# SCH_Line-Follower-proof-of-concepts_2025.net
KiCad netlist of a schematic drawn in EasyEDA
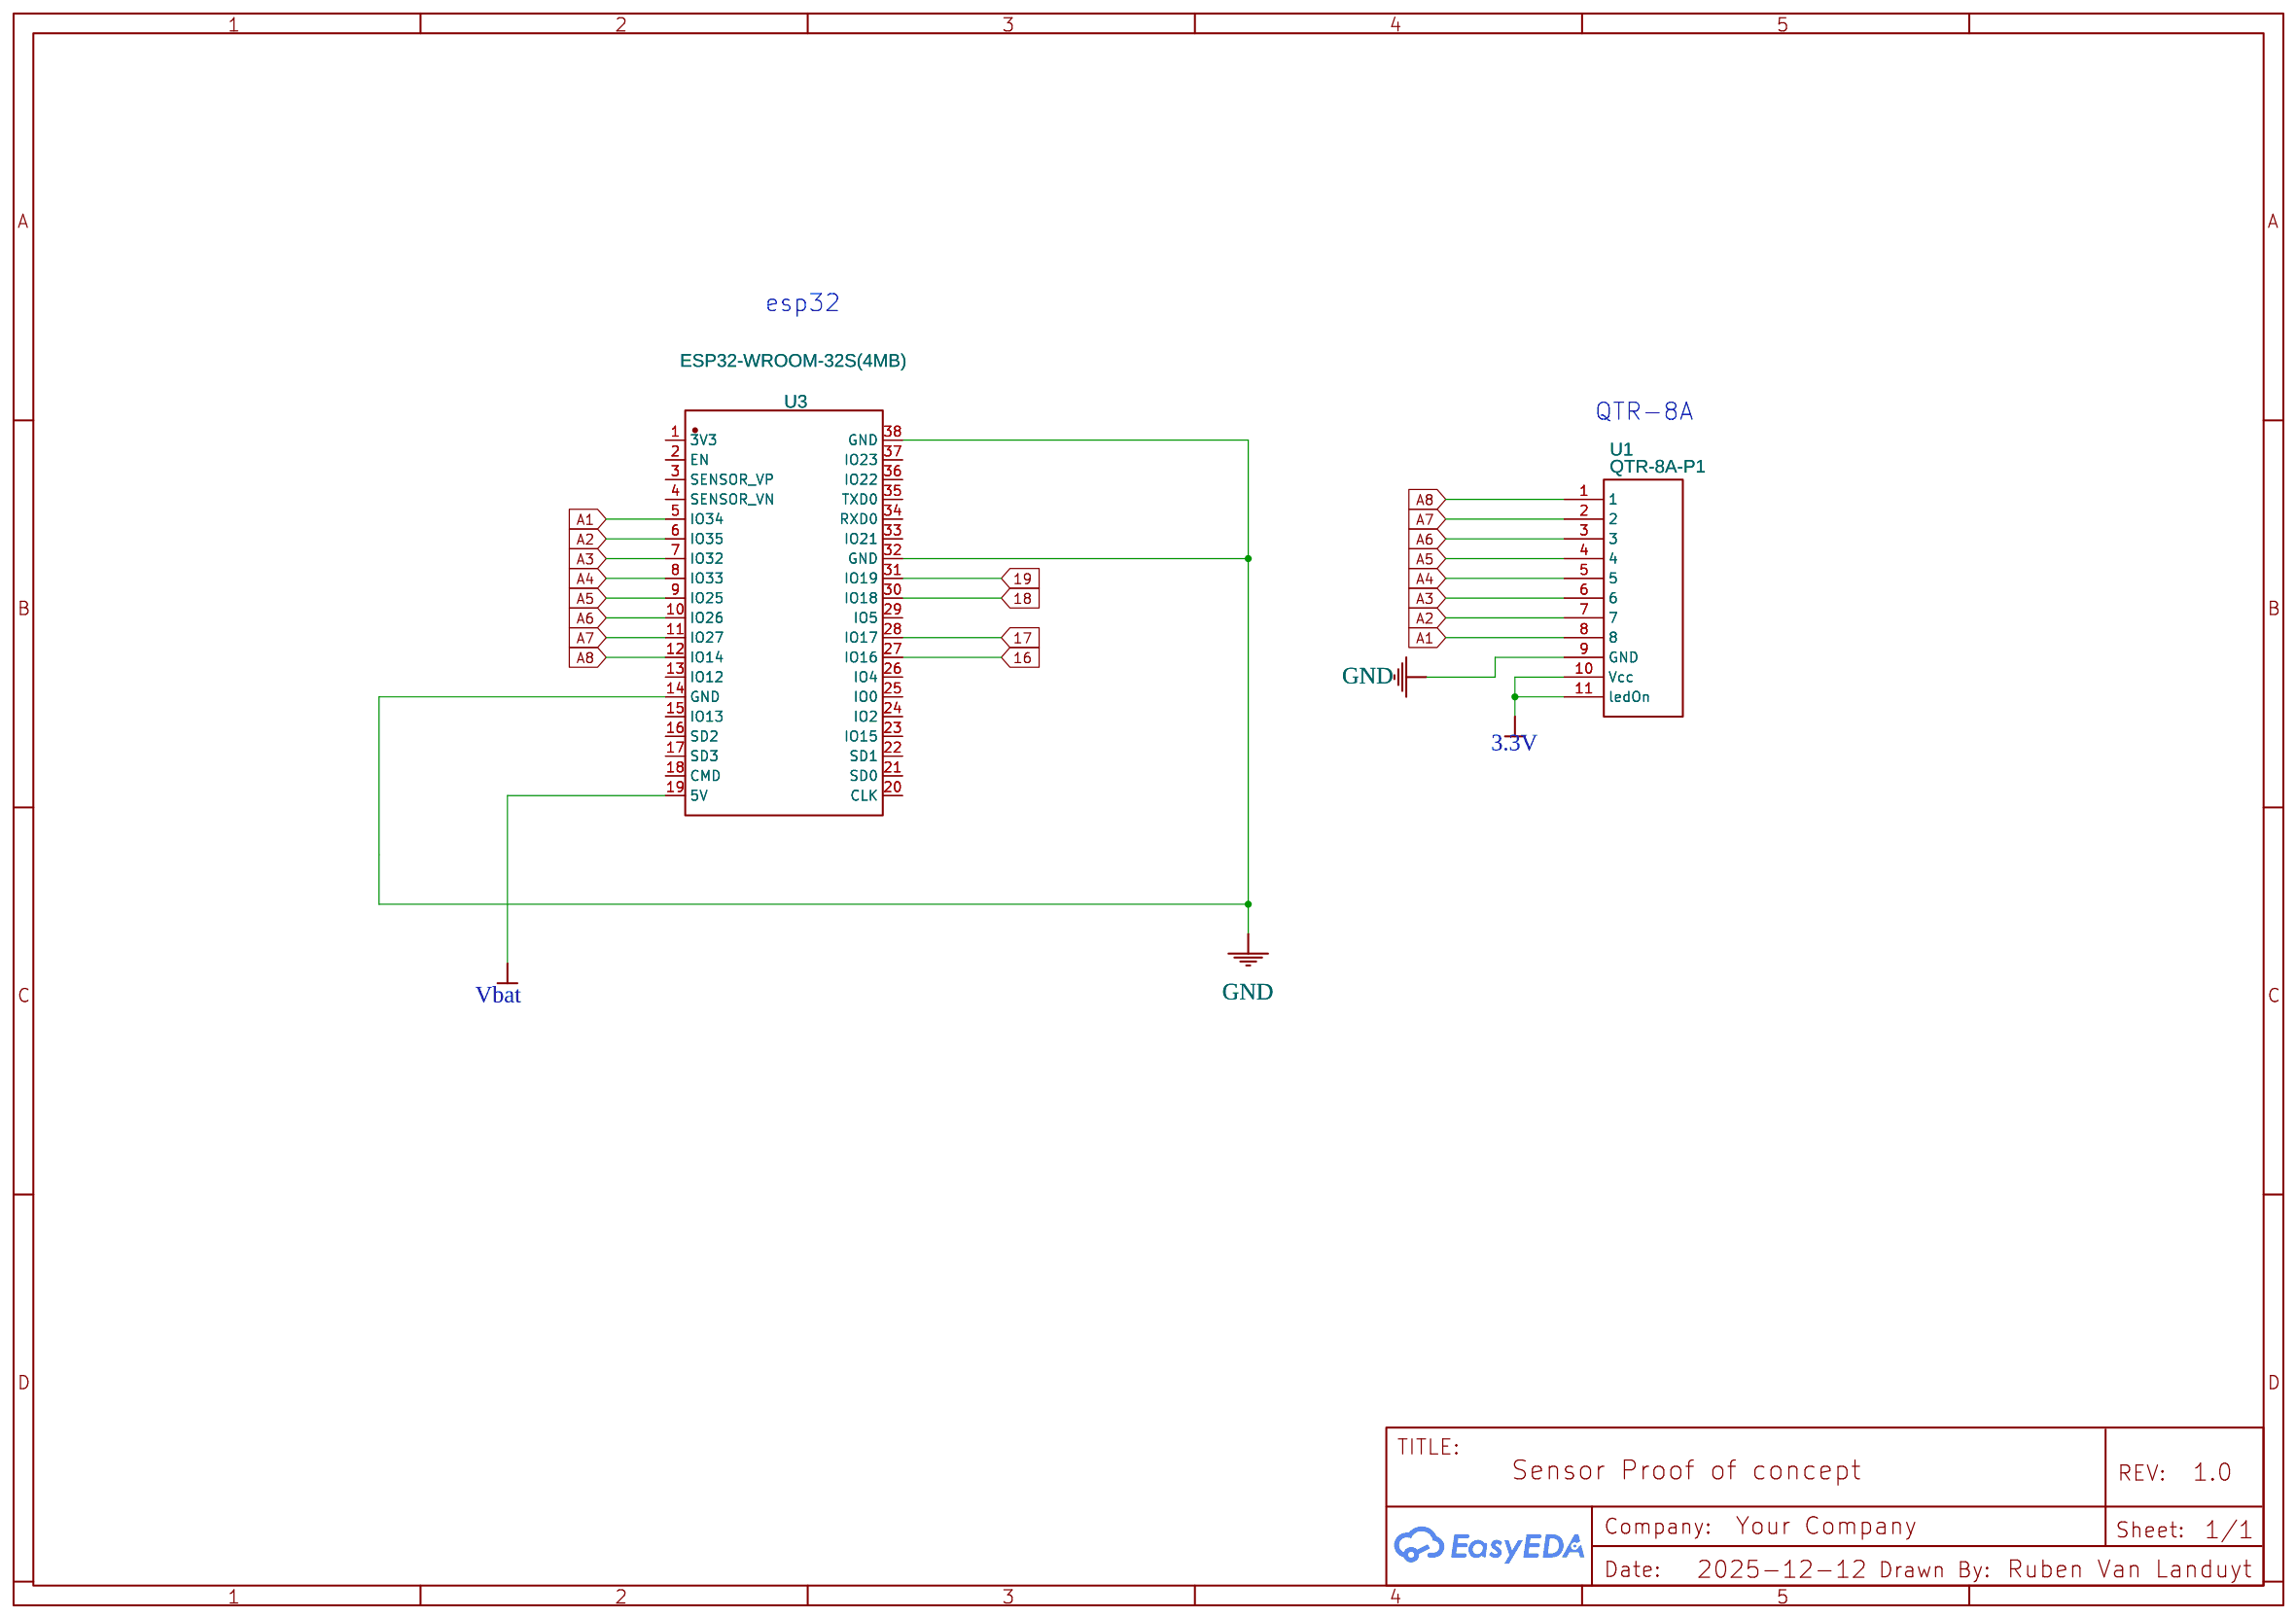
[diagram p0: Sensor proof of concept]
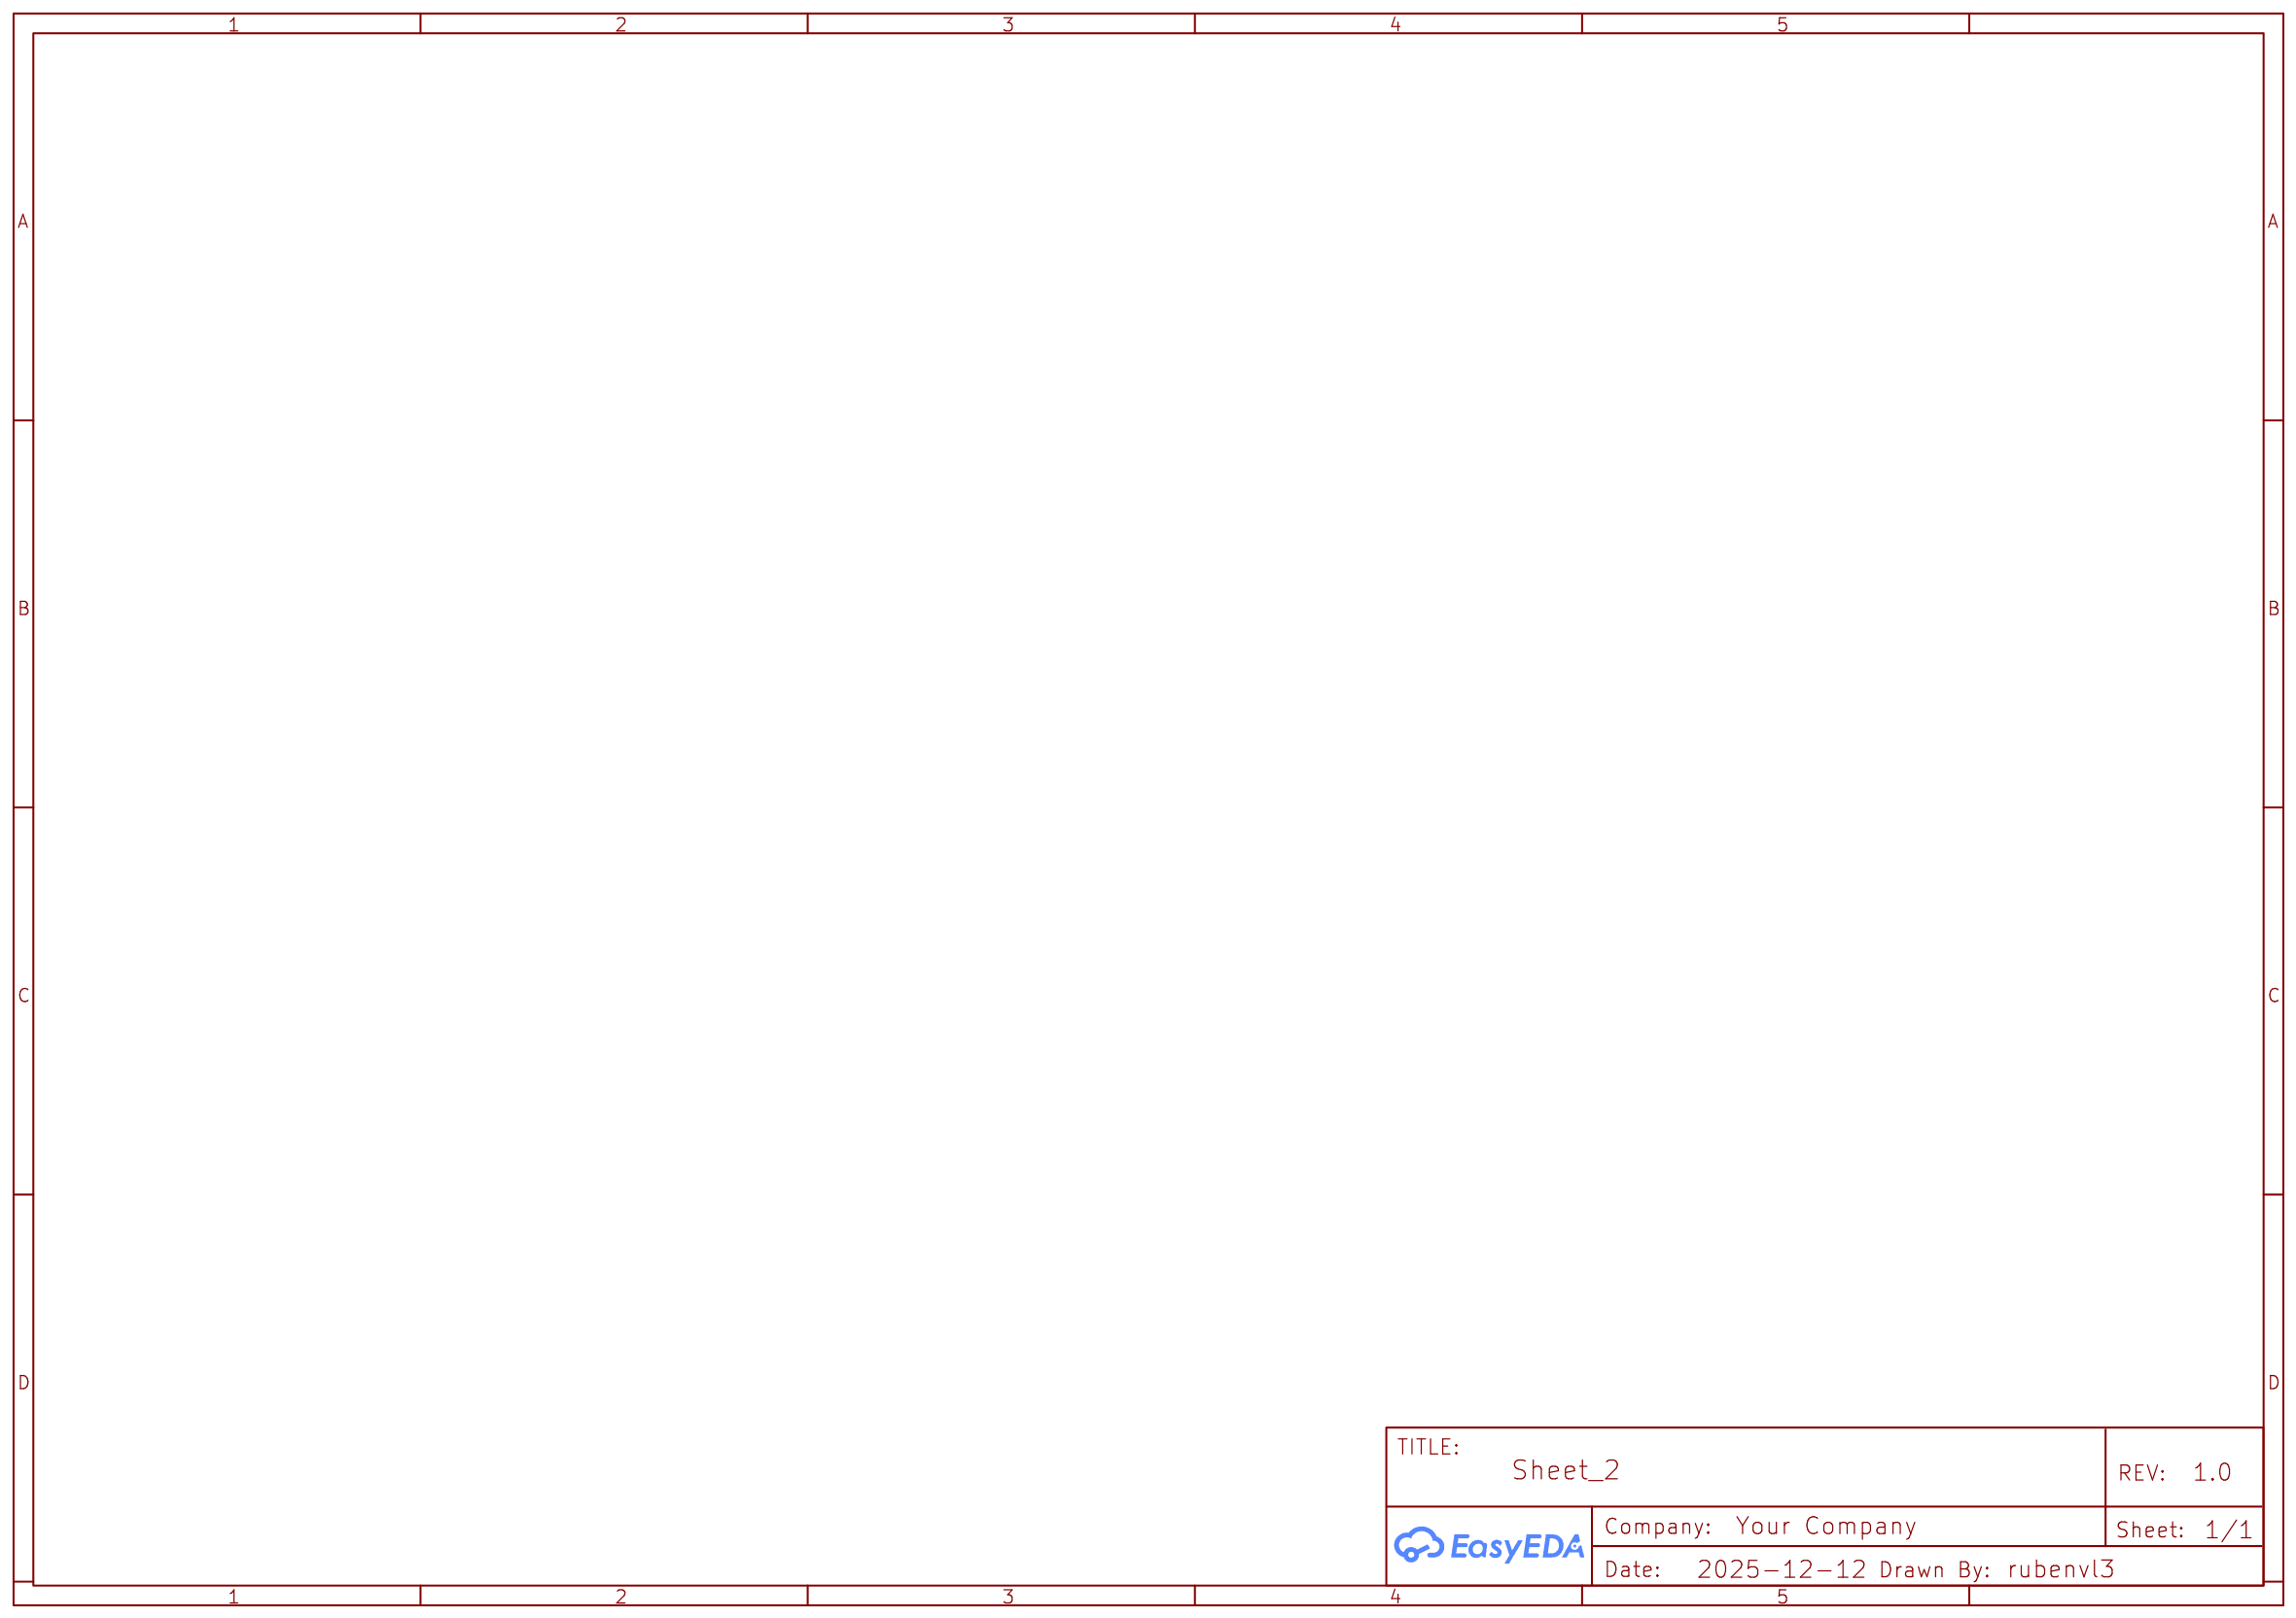
[diagram p1: Sheet_2]
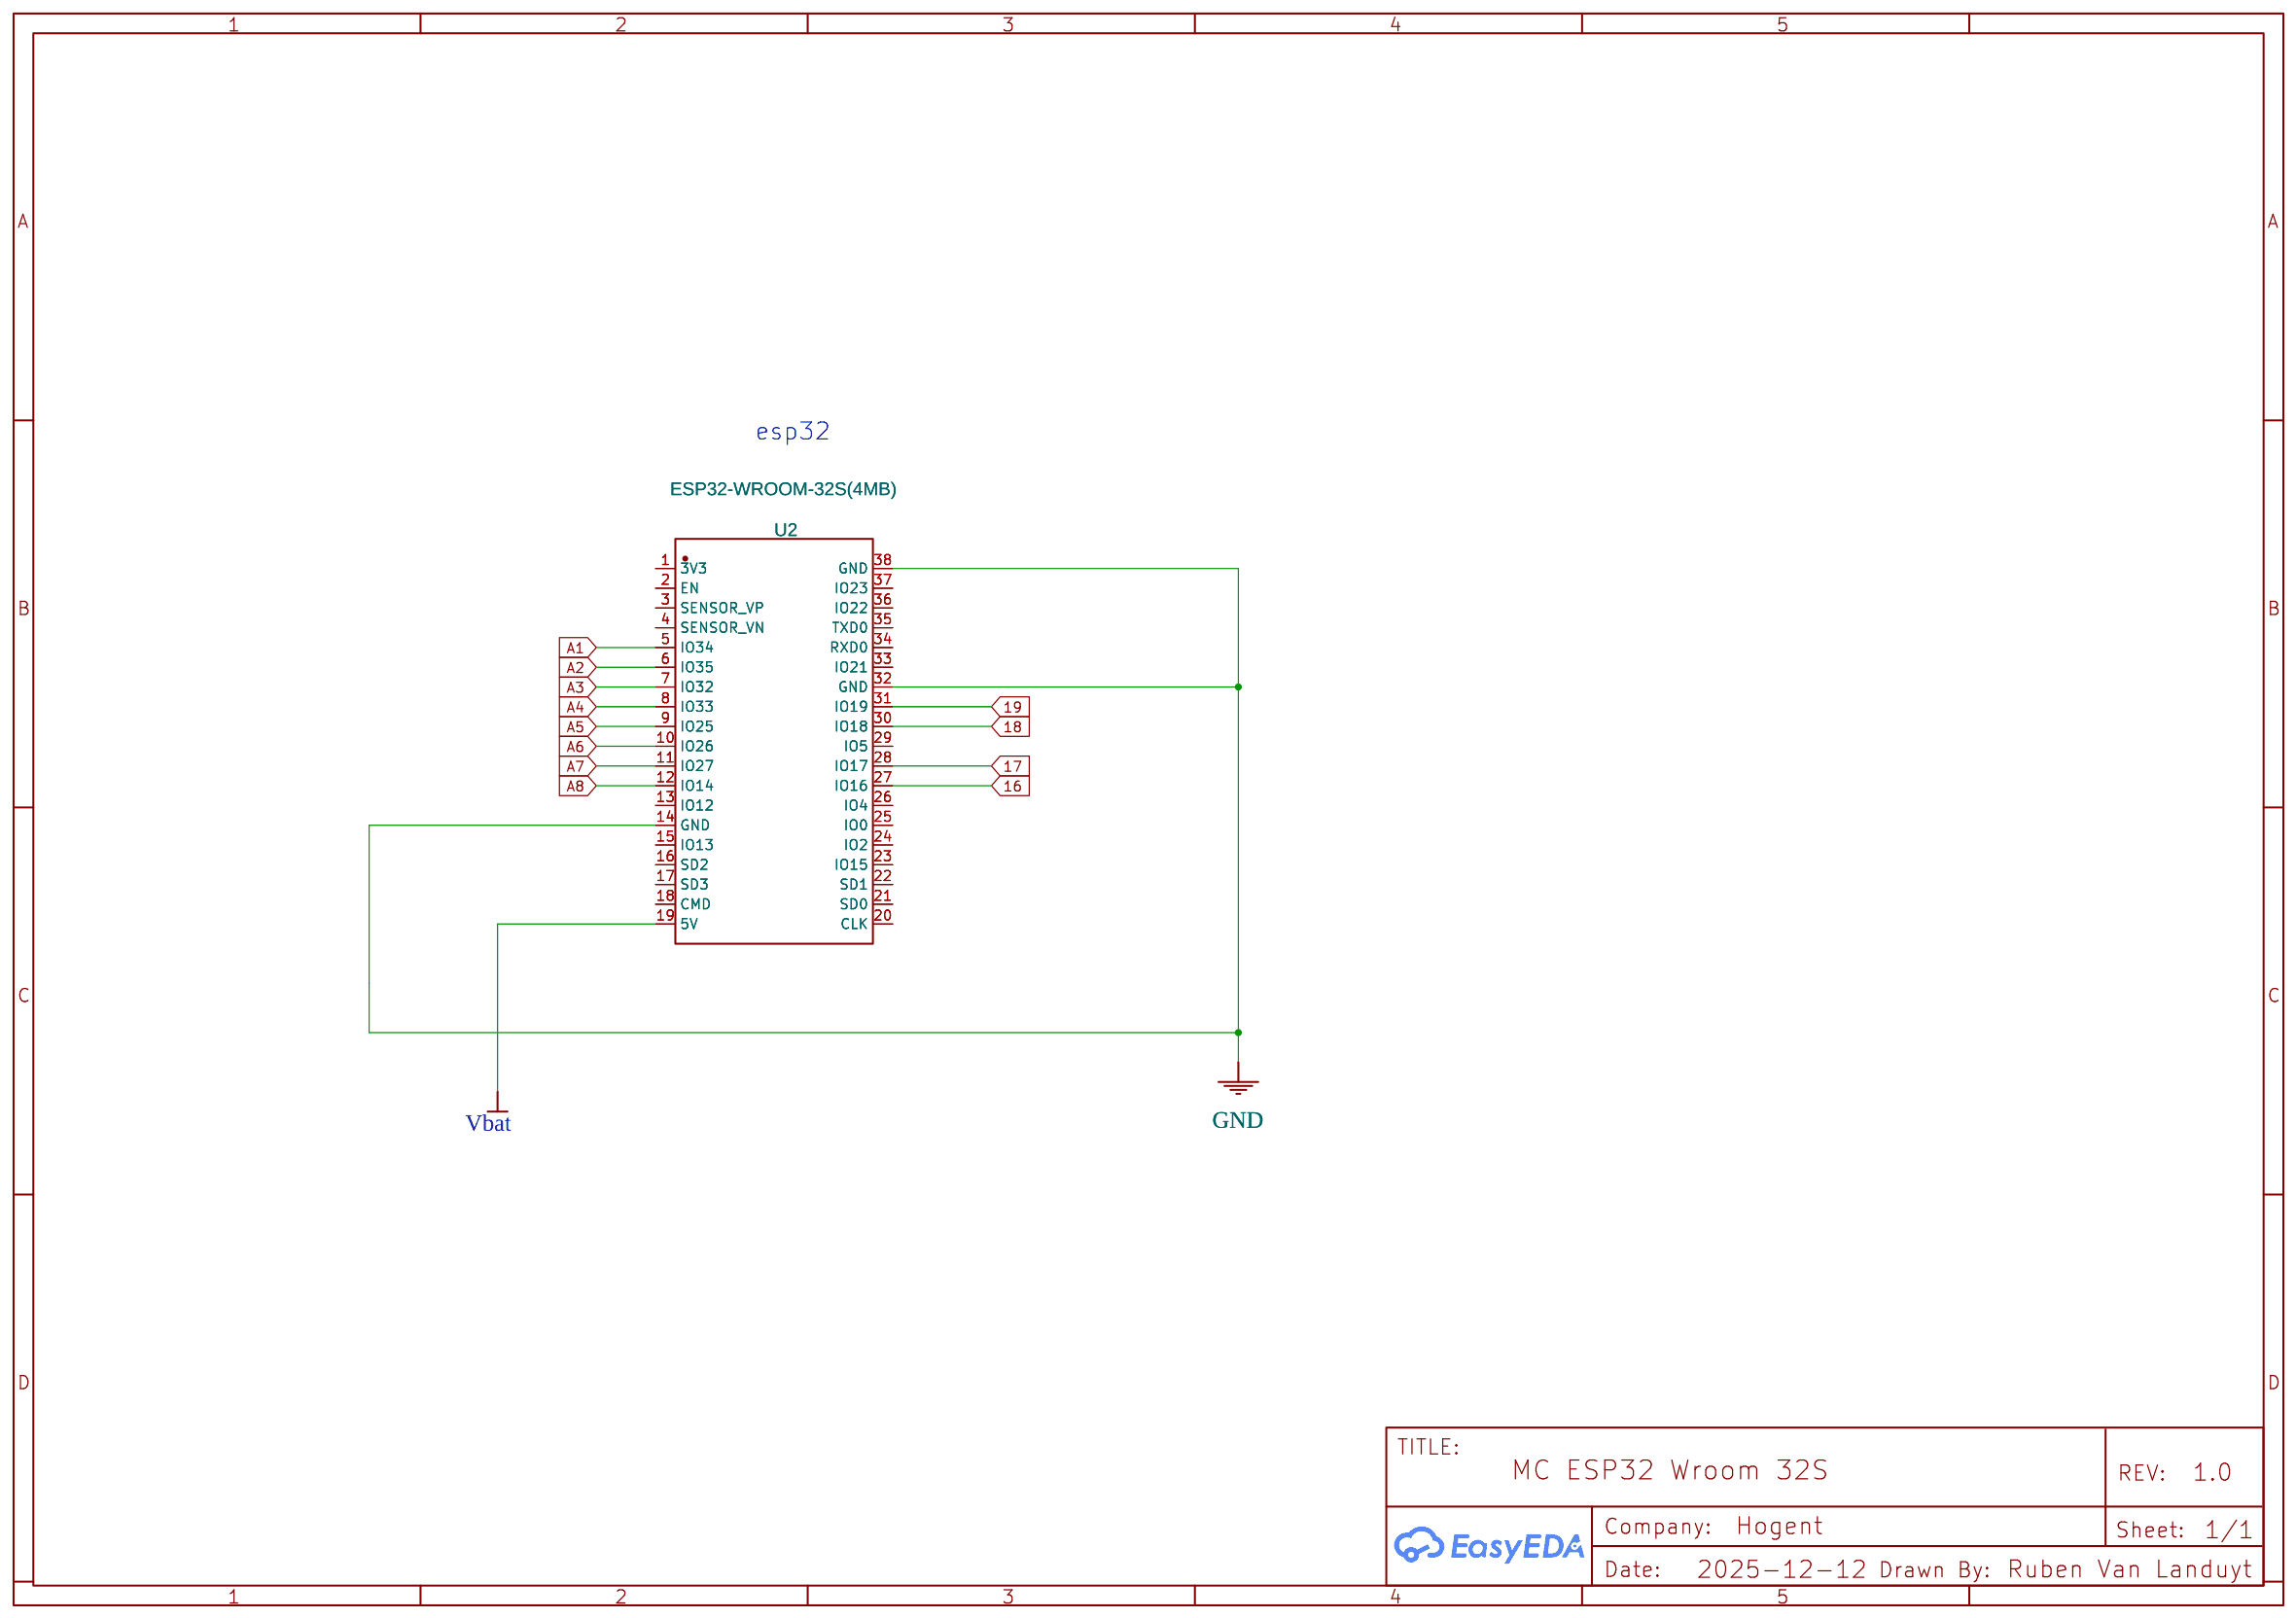
[diagram p2: ESP32 Wroom]

(export (version "E")
  (design (tool "Eeschema 10.0.6"))
  (components
    (comp (ref "U1") (value "QTR-8A-P1") (libsource (lib "") (part "QTR-8A-P1")))
    (comp (ref "U3")
      (value "ESP32-WROOM-32S(4MB)")
      (fields (field (name "Manufacturer") "Espressif Systems"))
      (libsource (lib "") (part "ESP32-WROOM-32S(4MB)"))
    )
    (comp (ref "U2")
      (value "ESP32-WROOM-32S(4MB)")
      (fields (field (name "Manufacturer") "Espressif Systems"))
      (libsource (lib "") (part "ESP32-WROOM-32S(4MB)"))
    )
  )
  (nets
    (net (code "1") (name "3.3V") (class "Default")
      (node (ref "U1") (pin "10") (pinfunction "Vcc_10") (pintype "unspecified"))
      (node (ref "U1") (pin "11") (pinfunction "ledOn_11") (pintype "unspecified"))
    )
    (net (code "2") (name "16") (class "Default")
      (node (ref "U2") (pin "27") (pinfunction "IO16_27") (pintype "unspecified"))
      (node (ref "U3") (pin "27") (pinfunction "IO16_27") (pintype "unspecified"))
    )
    (net (code "3") (name "17") (class "Default")
      (node (ref "U2") (pin "28") (pinfunction "IO17_28") (pintype "unspecified"))
      (node (ref "U3") (pin "28") (pinfunction "IO17_28") (pintype "unspecified"))
    )
    (net (code "4") (name "18") (class "Default")
      (node (ref "U2") (pin "30") (pinfunction "IO18_30") (pintype "unspecified"))
      (node (ref "U3") (pin "30") (pinfunction "IO18_30") (pintype "unspecified"))
    )
    (net (code "5") (name "19") (class "Default")
      (node (ref "U2") (pin "31") (pinfunction "IO19_31") (pintype "unspecified"))
      (node (ref "U3") (pin "31") (pinfunction "IO19_31") (pintype "unspecified"))
    )
    (net (code "6") (name "A1") (class "Default")
      (node (ref "U1") (pin "8") (pinfunction "8_8") (pintype "unspecified"))
      (node (ref "U2") (pin "5") (pinfunction "IO34_5") (pintype "unspecified"))
      (node (ref "U3") (pin "5") (pinfunction "IO34_5") (pintype "unspecified"))
    )
    (net (code "7") (name "A2") (class "Default")
      (node (ref "U1") (pin "7") (pinfunction "7_7") (pintype "unspecified"))
      (node (ref "U2") (pin "6") (pinfunction "IO35_6") (pintype "unspecified"))
      (node (ref "U3") (pin "6") (pinfunction "IO35_6") (pintype "unspecified"))
    )
    (net (code "8") (name "A3") (class "Default")
      (node (ref "U1") (pin "6") (pinfunction "6_6") (pintype "unspecified"))
      (node (ref "U2") (pin "7") (pinfunction "IO32_7") (pintype "unspecified"))
      (node (ref "U3") (pin "7") (pinfunction "IO32_7") (pintype "unspecified"))
    )
    (net (code "9") (name "A4") (class "Default")
      (node (ref "U1") (pin "5") (pinfunction "5_5") (pintype "unspecified"))
      (node (ref "U2") (pin "8") (pinfunction "IO33_8") (pintype "unspecified"))
      (node (ref "U3") (pin "8") (pinfunction "IO33_8") (pintype "unspecified"))
    )
    (net (code "10") (name "A5") (class "Default")
      (node (ref "U1") (pin "4") (pinfunction "4_4") (pintype "unspecified"))
      (node (ref "U2") (pin "9") (pinfunction "IO25_9") (pintype "unspecified"))
      (node (ref "U3") (pin "9") (pinfunction "IO25_9") (pintype "unspecified"))
    )
    (net (code "11") (name "A6") (class "Default")
      (node (ref "U1") (pin "3") (pinfunction "3_3") (pintype "unspecified"))
      (node (ref "U2") (pin "10") (pinfunction "IO26_10") (pintype "unspecified"))
      (node (ref "U3") (pin "10") (pinfunction "IO26_10") (pintype "unspecified"))
    )
    (net (code "12") (name "A7") (class "Default")
      (node (ref "U1") (pin "2") (pinfunction "2_2") (pintype "unspecified"))
      (node (ref "U2") (pin "11") (pinfunction "IO27_11") (pintype "unspecified"))
      (node (ref "U3") (pin "11") (pinfunction "IO27_11") (pintype "unspecified"))
    )
    (net (code "13") (name "A8") (class "Default")
      (node (ref "U1") (pin "1") (pinfunction "1_1") (pintype "unspecified"))
      (node (ref "U2") (pin "12") (pinfunction "IO14_12") (pintype "unspecified"))
      (node (ref "U3") (pin "12") (pinfunction "IO14_12") (pintype "unspecified"))
    )
    (net (code "14") (name "GND") (class "Default")
      (node (ref "U1") (pin "9") (pinfunction "GND_9") (pintype "unspecified"))
      (node (ref "U2") (pin "14") (pinfunction "GND_14") (pintype "unspecified"))
      (node (ref "U2") (pin "32") (pinfunction "GND_32") (pintype "unspecified"))
      (node (ref "U2") (pin "38") (pinfunction "GND_38") (pintype "unspecified"))
      (node (ref "U3") (pin "14") (pinfunction "GND_14") (pintype "unspecified"))
      (node (ref "U3") (pin "32") (pinfunction "GND_32") (pintype "unspecified"))
      (node (ref "U3") (pin "38") (pinfunction "GND_38") (pintype "unspecified"))
    )
    (net (code "15") (name "Vbat") (class "Default")
      (node (ref "U2") (pin "19") (pinfunction "5V_19") (pintype "unspecified"))
      (node (ref "U3") (pin "19") (pinfunction "5V_19") (pintype "unspecified"))
    )
    (net (code "16") (name "unconnected-(U2-3V3-Pad1)") (class "Default")
      (node (ref "U2") (pin "1") (pinfunction "3V3_1") (pintype "unspecified"))
    )
    (net (code "17") (name "unconnected-(U2-CLK-Pad20)") (class "Default")
      (node (ref "U2") (pin "20") (pinfunction "CLK_20") (pintype "unspecified"))
    )
    (net (code "18") (name "unconnected-(U2-CMD-Pad18)") (class "Default")
      (node (ref "U2") (pin "18") (pinfunction "CMD_18") (pintype "unspecified"))
    )
    (net (code "19") (name "unconnected-(U2-EN-Pad2)") (class "Default")
      (node (ref "U2") (pin "2") (pinfunction "EN_2") (pintype "unspecified"))
    )
    (net (code "20") (name "unconnected-(U2-IO0-Pad25)") (class "Default")
      (node (ref "U2") (pin "25") (pinfunction "IO0_25") (pintype "unspecified"))
    )
    (net (code "21") (name "unconnected-(U2-IO2-Pad24)") (class "Default")
      (node (ref "U2") (pin "24") (pinfunction "IO2_24") (pintype "unspecified"))
    )
    (net (code "22") (name "unconnected-(U2-IO4-Pad26)") (class "Default")
      (node (ref "U2") (pin "26") (pinfunction "IO4_26") (pintype "unspecified"))
    )
    (net (code "23") (name "unconnected-(U2-IO5-Pad29)") (class "Default")
      (node (ref "U2") (pin "29") (pinfunction "IO5_29") (pintype "unspecified"))
    )
    (net (code "24") (name "unconnected-(U2-IO12-Pad13)") (class "Default")
      (node (ref "U2") (pin "13") (pinfunction "IO12_13") (pintype "unspecified"))
    )
    (net (code "25") (name "unconnected-(U2-IO13-Pad15)") (class "Default")
      (node (ref "U2") (pin "15") (pinfunction "IO13_15") (pintype "unspecified"))
    )
    (net (code "26") (name "unconnected-(U2-IO15-Pad23)") (class "Default")
      (node (ref "U2") (pin "23") (pinfunction "IO15_23") (pintype "unspecified"))
    )
    (net (code "27") (name "unconnected-(U2-IO21-Pad33)") (class "Default")
      (node (ref "U2") (pin "33") (pinfunction "IO21_33") (pintype "unspecified"))
    )
    (net (code "28") (name "unconnected-(U2-IO22-Pad36)") (class "Default")
      (node (ref "U2") (pin "36") (pinfunction "IO22_36") (pintype "unspecified"))
    )
    (net (code "29") (name "unconnected-(U2-IO23-Pad37)") (class "Default")
      (node (ref "U2") (pin "37") (pinfunction "IO23_37") (pintype "unspecified"))
    )
    (net (code "30") (name "unconnected-(U2-RXD0-Pad34)") (class "Default")
      (node (ref "U2") (pin "34") (pinfunction "RXD0_34") (pintype "unspecified"))
    )
    (net (code "31") (name "unconnected-(U2-SD0-Pad21)") (class "Default")
      (node (ref "U2") (pin "21") (pinfunction "SD0_21") (pintype "unspecified"))
    )
    (net (code "32") (name "unconnected-(U2-SD1-Pad22)") (class "Default")
      (node (ref "U2") (pin "22") (pinfunction "SD1_22") (pintype "unspecified"))
    )
    (net (code "33") (name "unconnected-(U2-SD2-Pad16)") (class "Default")
      (node (ref "U2") (pin "16") (pinfunction "SD2_16") (pintype "unspecified"))
    )
    (net (code "34") (name "unconnected-(U2-SD3-Pad17)") (class "Default")
      (node (ref "U2") (pin "17") (pinfunction "SD3_17") (pintype "unspecified"))
    )
    (net (code "35") (name "unconnected-(U2-SENSOR_VN-Pad4)") (class "Default")
      (node (ref "U2") (pin "4") (pinfunction "SENSOR_VN_4") (pintype "unspecified"))
    )
    (net (code "36") (name "unconnected-(U2-SENSOR_VP-Pad3)") (class "Default")
      (node (ref "U2") (pin "3") (pinfunction "SENSOR_VP_3") (pintype "unspecified"))
    )
    (net (code "37") (name "unconnected-(U2-TXD0-Pad35)") (class "Default")
      (node (ref "U2") (pin "35") (pinfunction "TXD0_35") (pintype "unspecified"))
    )
    (net (code "38") (name "unconnected-(U3-3V3-Pad1)") (class "Default")
      (node (ref "U3") (pin "1") (pinfunction "3V3_1") (pintype "unspecified"))
    )
    (net (code "39") (name "unconnected-(U3-CLK-Pad20)") (class "Default")
      (node (ref "U3") (pin "20") (pinfunction "CLK_20") (pintype "unspecified"))
    )
    (net (code "40") (name "unconnected-(U3-CMD-Pad18)") (class "Default")
      (node (ref "U3") (pin "18") (pinfunction "CMD_18") (pintype "unspecified"))
    )
    (net (code "41") (name "unconnected-(U3-EN-Pad2)") (class "Default")
      (node (ref "U3") (pin "2") (pinfunction "EN_2") (pintype "unspecified"))
    )
    (net (code "42") (name "unconnected-(U3-IO0-Pad25)") (class "Default")
      (node (ref "U3") (pin "25") (pinfunction "IO0_25") (pintype "unspecified"))
    )
    (net (code "43") (name "unconnected-(U3-IO2-Pad24)") (class "Default")
      (node (ref "U3") (pin "24") (pinfunction "IO2_24") (pintype "unspecified"))
    )
    (net (code "44") (name "unconnected-(U3-IO4-Pad26)") (class "Default")
      (node (ref "U3") (pin "26") (pinfunction "IO4_26") (pintype "unspecified"))
    )
    (net (code "45") (name "unconnected-(U3-IO5-Pad29)") (class "Default")
      (node (ref "U3") (pin "29") (pinfunction "IO5_29") (pintype "unspecified"))
    )
    (net (code "46") (name "unconnected-(U3-IO12-Pad13)") (class "Default")
      (node (ref "U3") (pin "13") (pinfunction "IO12_13") (pintype "unspecified"))
    )
    (net (code "47") (name "unconnected-(U3-IO13-Pad15)") (class "Default")
      (node (ref "U3") (pin "15") (pinfunction "IO13_15") (pintype "unspecified"))
    )
    (net (code "48") (name "unconnected-(U3-IO15-Pad23)") (class "Default")
      (node (ref "U3") (pin "23") (pinfunction "IO15_23") (pintype "unspecified"))
    )
    (net (code "49") (name "unconnected-(U3-IO21-Pad33)") (class "Default")
      (node (ref "U3") (pin "33") (pinfunction "IO21_33") (pintype "unspecified"))
    )
    (net (code "50") (name "unconnected-(U3-IO22-Pad36)") (class "Default")
      (node (ref "U3") (pin "36") (pinfunction "IO22_36") (pintype "unspecified"))
    )
    (net (code "51") (name "unconnected-(U3-IO23-Pad37)") (class "Default")
      (node (ref "U3") (pin "37") (pinfunction "IO23_37") (pintype "unspecified"))
    )
    (net (code "52") (name "unconnected-(U3-RXD0-Pad34)") (class "Default")
      (node (ref "U3") (pin "34") (pinfunction "RXD0_34") (pintype "unspecified"))
    )
    (net (code "53") (name "unconnected-(U3-SD0-Pad21)") (class "Default")
      (node (ref "U3") (pin "21") (pinfunction "SD0_21") (pintype "unspecified"))
    )
    (net (code "54") (name "unconnected-(U3-SD1-Pad22)") (class "Default")
      (node (ref "U3") (pin "22") (pinfunction "SD1_22") (pintype "unspecified"))
    )
    (net (code "55") (name "unconnected-(U3-SD2-Pad16)") (class "Default")
      (node (ref "U3") (pin "16") (pinfunction "SD2_16") (pintype "unspecified"))
    )
    (net (code "56") (name "unconnected-(U3-SD3-Pad17)") (class "Default")
      (node (ref "U3") (pin "17") (pinfunction "SD3_17") (pintype "unspecified"))
    )
    (net (code "57") (name "unconnected-(U3-SENSOR_VN-Pad4)") (class "Default")
      (node (ref "U3") (pin "4") (pinfunction "SENSOR_VN_4") (pintype "unspecified"))
    )
    (net (code "58") (name "unconnected-(U3-SENSOR_VP-Pad3)") (class "Default")
      (node (ref "U3") (pin "3") (pinfunction "SENSOR_VP_3") (pintype "unspecified"))
    )
    (net (code "59") (name "unconnected-(U3-TXD0-Pad35)") (class "Default")
      (node (ref "U3") (pin "35") (pinfunction "TXD0_35") (pintype "unspecified"))
    )
  )
)
